# MC10_Tape.net
KiCad netlist of a schematic drawn in EAGLE
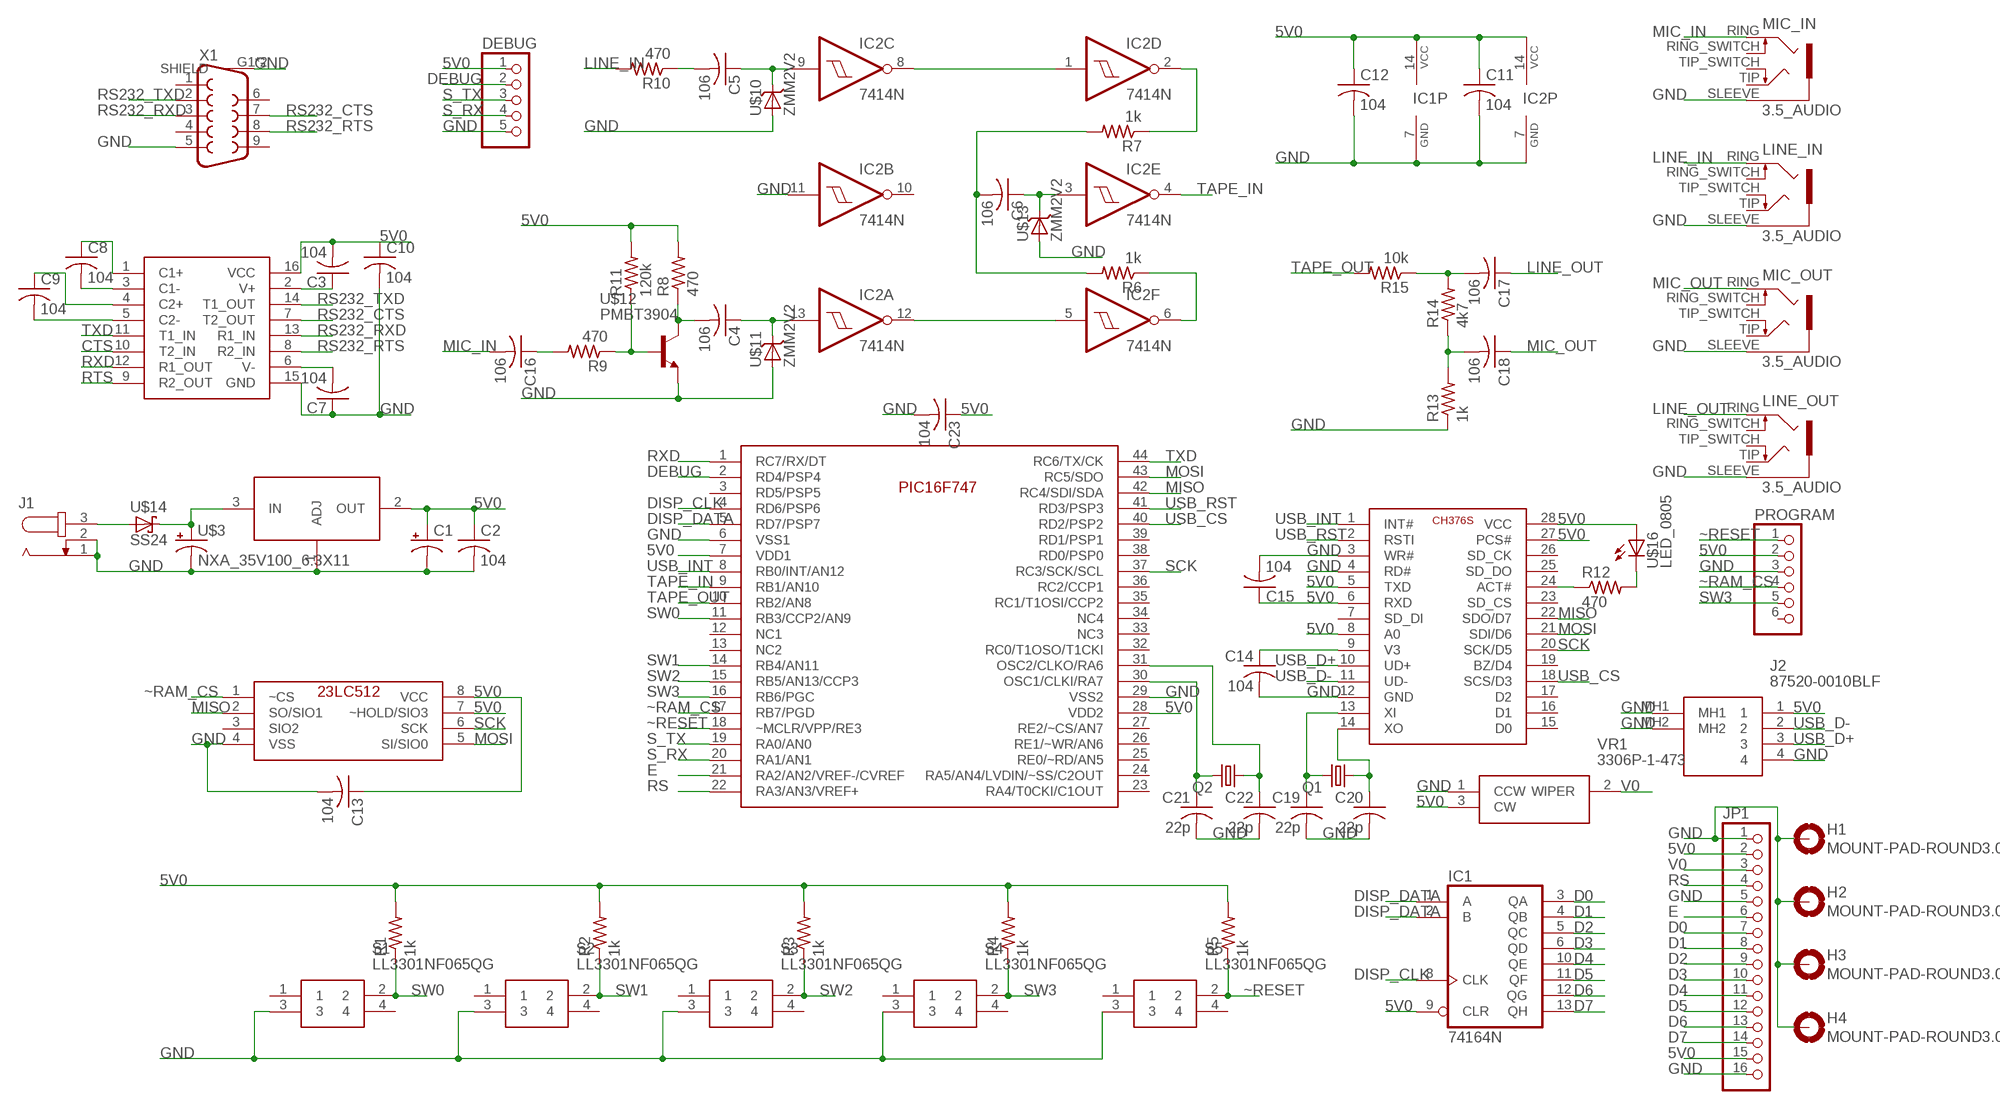
[diagram p0: schematic, sheet 1]

(export (version "E")
  (design (tool "Eeschema 10.0.6"))
  (components
    (comp (ref "C1")
      (value "CPOL-USUD-6,3X5,8")
      (footprint "eagle-import:UD-6,3X5,8_NICHICON")
      (libsource (lib "eagle-import") (part "CPOL-USUD-6,3X5,8"))
    )
    (comp (ref "C2")
      (value "104")
      (footprint "eagle-import:C0805")
      (libsource (lib "eagle-import") (part "C-USC0805"))
    )
    (comp (ref "C3")
      (value "104")
      (footprint "eagle-import:C0805")
      (libsource (lib "eagle-import") (part "C-USC0805"))
    )
    (comp (ref "C4")
      (value "106")
      (footprint "eagle-import:C1206")
      (libsource (lib "eagle-import") (part "C-USC1206"))
    )
    (comp (ref "C5")
      (value "106")
      (footprint "eagle-import:C1206")
      (libsource (lib "eagle-import") (part "C-USC1206"))
    )
    (comp (ref "C6")
      (value "106")
      (footprint "eagle-import:C1206")
      (libsource (lib "eagle-import") (part "C-USC1206"))
    )
    (comp (ref "C7")
      (value "104")
      (footprint "eagle-import:C0805")
      (libsource (lib "eagle-import") (part "C-USC0805"))
    )
    (comp (ref "C8")
      (value "104")
      (footprint "eagle-import:C0805")
      (libsource (lib "eagle-import") (part "C-USC0805"))
    )
    (comp (ref "C9")
      (value "104")
      (footprint "eagle-import:C0805")
      (libsource (lib "eagle-import") (part "C-USC0805"))
    )
    (comp (ref "C10")
      (value "104")
      (footprint "eagle-import:C0805")
      (libsource (lib "eagle-import") (part "C-USC0805"))
    )
    (comp (ref "C11")
      (value "104")
      (footprint "eagle-import:C0805")
      (libsource (lib "eagle-import") (part "C-USC0805"))
    )
    (comp (ref "C12")
      (value "104")
      (footprint "eagle-import:C0805")
      (libsource (lib "eagle-import") (part "C-USC0805"))
    )
    (comp (ref "C13")
      (value "104")
      (footprint "eagle-import:C0805")
      (libsource (lib "eagle-import") (part "C-USC0805"))
    )
    (comp (ref "C14")
      (value "104")
      (footprint "eagle-import:C0805")
      (libsource (lib "eagle-import") (part "C-USC0805"))
    )
    (comp (ref "C15")
      (value "104")
      (footprint "eagle-import:C0805")
      (libsource (lib "eagle-import") (part "C-USC0805"))
    )
    (comp (ref "C16")
      (value "106")
      (footprint "eagle-import:C1206")
      (libsource (lib "eagle-import") (part "C-USC1206"))
    )
    (comp (ref "C17")
      (value "106")
      (footprint "eagle-import:C1206")
      (libsource (lib "eagle-import") (part "C-USC1206"))
    )
    (comp (ref "C18")
      (value "106")
      (footprint "eagle-import:C1206")
      (libsource (lib "eagle-import") (part "C-USC1206"))
    )
    (comp (ref "C19")
      (value "22p")
      (footprint "eagle-import:C0805")
      (libsource (lib "eagle-import") (part "C-USC0805"))
    )
    (comp (ref "C20")
      (value "22p")
      (footprint "eagle-import:C0805")
      (libsource (lib "eagle-import") (part "C-USC0805"))
    )
    (comp (ref "C21")
      (value "22p")
      (footprint "eagle-import:C0805")
      (libsource (lib "eagle-import") (part "C-USC0805"))
    )
    (comp (ref "C22")
      (value "22p")
      (footprint "eagle-import:C0805")
      (libsource (lib "eagle-import") (part "C-USC0805"))
    )
    (comp (ref "C23")
      (value "104")
      (footprint "eagle-import:C0805")
      (libsource (lib "eagle-import") (part "C-USC0805"))
    )
    (comp (ref "DEBUG")
      (value "PINHD-1X5")
      (footprint "eagle-import:1X05")
      (libsource (lib "eagle-import") (part "PINHD-1X5"))
    )
    (comp (ref "H1")
      (value "MOUNT-PAD-ROUND3.0")
      (footprint "eagle-import:3,0-PAD")
      (libsource (lib "eagle-import") (part "MOUNT-PAD-ROUND3.0"))
    )
    (comp (ref "H2")
      (value "MOUNT-PAD-ROUND3.0")
      (footprint "eagle-import:3,0-PAD")
      (libsource (lib "eagle-import") (part "MOUNT-PAD-ROUND3.0"))
    )
    (comp (ref "H3")
      (value "MOUNT-PAD-ROUND3.0")
      (footprint "eagle-import:3,0-PAD")
      (libsource (lib "eagle-import") (part "MOUNT-PAD-ROUND3.0"))
    )
    (comp (ref "H4")
      (value "MOUNT-PAD-ROUND3.0")
      (footprint "eagle-import:3,0-PAD")
      (libsource (lib "eagle-import") (part "MOUNT-PAD-ROUND3.0"))
    )
    (comp (ref "IC1")
      (value "74164N")
      (footprint "eagle-import:DIL14")
      (libsource (lib "eagle-import") (part "74164N"))
    )
    (comp (ref "IC2")
      (value "7414N")
      (footprint "eagle-import:DIL14")
      (libsource (lib "eagle-import") (part "7414N"))
    )
    (comp (ref "J1")
      (value "JACK-PLUG0")
      (footprint "eagle-import:SPC4077")
      (libsource (lib "eagle-import") (part "JACK-PLUG0"))
    )
    (comp (ref "J2")
      (value "87520-0010BLF")
      (footprint "eagle-import:875200010BLF")
      (fields (field (name "MOUSER_PART_NUMBER") "649-87520-0010BLF"))
      (libsource (lib "eagle-import") (part "87520-0010BLF"))
    )
    (comp (ref "JP1")
      (value "PINHD-1X16")
      (footprint "eagle-import:1X16")
      (libsource (lib "eagle-import") (part "PINHD-1X16"))
    )
    (comp (ref "LINE_IN")
      (value "3.5_AUDIO")
      (footprint "eagle-import:3.5_AUDIO")
      (libsource (lib "eagle-import") (part "3.5_AUDIO"))
    )
    (comp (ref "LINE_OUT")
      (value "3.5_AUDIO")
      (footprint "eagle-import:3.5_AUDIO")
      (libsource (lib "eagle-import") (part "3.5_AUDIO"))
    )
    (comp (ref "MIC_IN")
      (value "3.5_AUDIO")
      (footprint "eagle-import:3.5_AUDIO")
      (libsource (lib "eagle-import") (part "3.5_AUDIO"))
    )
    (comp (ref "MIC_OUT")
      (value "3.5_AUDIO")
      (footprint "eagle-import:3.5_AUDIO")
      (libsource (lib "eagle-import") (part "3.5_AUDIO"))
    )
    (comp (ref "PROGRAM")
      (value "PINHD-1X6")
      (footprint "eagle-import:1X06")
      (libsource (lib "eagle-import") (part "PINHD-1X6"))
    )
    (comp (ref "Q1")
      (value "CRYSTALHC49S")
      (footprint "eagle-import:HC49_S")
      (libsource (lib "eagle-import") (part "CRYSTALHC49S"))
    )
    (comp (ref "Q2")
      (value "CRYSTALHC49S")
      (footprint "eagle-import:HC49_S")
      (libsource (lib "eagle-import") (part "CRYSTALHC49S"))
    )
    (comp (ref "R1")
      (value "1k")
      (footprint "eagle-import:M0805")
      (libsource (lib "eagle-import") (part "R-US_M0805"))
    )
    (comp (ref "R2")
      (value "1k")
      (footprint "eagle-import:M0805")
      (libsource (lib "eagle-import") (part "R-US_M0805"))
    )
    (comp (ref "R3")
      (value "1k")
      (footprint "eagle-import:M0805")
      (libsource (lib "eagle-import") (part "R-US_M0805"))
    )
    (comp (ref "R4")
      (value "1k")
      (footprint "eagle-import:M0805")
      (libsource (lib "eagle-import") (part "R-US_M0805"))
    )
    (comp (ref "R5")
      (value "1k")
      (footprint "eagle-import:M0805")
      (libsource (lib "eagle-import") (part "R-US_M0805"))
    )
    (comp (ref "R6")
      (value "1k")
      (footprint "eagle-import:M0805")
      (libsource (lib "eagle-import") (part "R-US_M0805"))
    )
    (comp (ref "R7")
      (value "1k")
      (footprint "eagle-import:M0805")
      (libsource (lib "eagle-import") (part "R-US_M0805"))
    )
    (comp (ref "R8")
      (value "470")
      (footprint "eagle-import:M0805")
      (libsource (lib "eagle-import") (part "R-US_M0805"))
    )
    (comp (ref "R9")
      (value "470")
      (footprint "eagle-import:M0805")
      (libsource (lib "eagle-import") (part "R-US_M0805"))
    )
    (comp (ref "R10")
      (value "470")
      (footprint "eagle-import:M0805")
      (libsource (lib "eagle-import") (part "R-US_M0805"))
    )
    (comp (ref "R11")
      (value "120k")
      (footprint "eagle-import:M0805")
      (libsource (lib "eagle-import") (part "R-US_M0805"))
    )
    (comp (ref "R12")
      (value "470")
      (footprint "eagle-import:M0805")
      (libsource (lib "eagle-import") (part "R-US_M0805"))
    )
    (comp (ref "R13")
      (value "1k")
      (footprint "eagle-import:M0805")
      (libsource (lib "eagle-import") (part "R-US_M0805"))
    )
    (comp (ref "R14")
      (value "4k7")
      (footprint "eagle-import:M0805")
      (libsource (lib "eagle-import") (part "R-US_M0805"))
    )
    (comp (ref "R15")
      (value "10k")
      (footprint "eagle-import:M0805")
      (libsource (lib "eagle-import") (part "R-US_M0805"))
    )
    (comp (ref "S1")
      (value "LL3301NF065QG")
      (footprint "eagle-import:LL3301NF065QG")
      (fields (field (name "MOUSER_PART_NUMBER") "612-LL3301NF065QG"))
      (libsource (lib "eagle-import") (part "LL3301NF065QG"))
    )
    (comp (ref "S2")
      (value "LL3301NF065QG")
      (footprint "eagle-import:LL3301NF065QG")
      (fields (field (name "MOUSER_PART_NUMBER") "612-LL3301NF065QG"))
      (libsource (lib "eagle-import") (part "LL3301NF065QG"))
    )
    (comp (ref "S3")
      (value "LL3301NF065QG")
      (footprint "eagle-import:LL3301NF065QG")
      (fields (field (name "MOUSER_PART_NUMBER") "612-LL3301NF065QG"))
      (libsource (lib "eagle-import") (part "LL3301NF065QG"))
    )
    (comp (ref "S4")
      (value "LL3301NF065QG")
      (footprint "eagle-import:LL3301NF065QG")
      (fields (field (name "MOUSER_PART_NUMBER") "612-LL3301NF065QG"))
      (libsource (lib "eagle-import") (part "LL3301NF065QG"))
    )
    (comp (ref "S5")
      (value "LL3301NF065QG")
      (footprint "eagle-import:LL3301NF065QG")
      (fields (field (name "MOUSER_PART_NUMBER") "612-LL3301NF065QG"))
      (libsource (lib "eagle-import") (part "LL3301NF065QG"))
    )
    (comp (ref "U$1")
      (value "PIC16F747-IPT")
      (footprint "eagle-import:TQFP44")
      (libsource (lib "eagle-import") (part "PIC16F747-IPT"))
    )
    (comp (ref "U$2")
      (value "LM1086")
      (footprint "eagle-import:D2PACK")
      (libsource (lib "eagle-import") (part "LM1086"))
    )
    (comp (ref "U$3")
      (value "NXA_35V100_6.3X11")
      (footprint "eagle-import:NXA_35V100_6.3X11")
      (libsource (lib "eagle-import") (part "NXA_35V100_6.3X11"))
    )
    (comp (ref "U$4")
      (value "23LC512T-ISN")
      (footprint "eagle-import:SO08")
      (libsource (lib "eagle-import") (part "23LC512T-ISN"))
    )
    (comp (ref "U$9")
      (value "SP232")
      (footprint "eagle-import:SOP16")
      (libsource (lib "eagle-import") (part "SP232"))
    )
    (comp (ref "U$10")
      (value "ZMM2V2")
      (footprint "eagle-import:SOD80C")
      (libsource (lib "eagle-import") (part "ZMM2V2"))
    )
    (comp (ref "U$11")
      (value "ZMM2V2")
      (footprint "eagle-import:SOD80C")
      (libsource (lib "eagle-import") (part "ZMM2V2"))
    )
    (comp (ref "U$12")
      (value "PMBT3904")
      (footprint "eagle-import:SOT23")
      (libsource (lib "eagle-import") (part "PMBT3904"))
    )
    (comp (ref "U$13")
      (value "ZMM2V2")
      (footprint "eagle-import:SOD80C")
      (libsource (lib "eagle-import") (part "ZMM2V2"))
    )
    (comp (ref "U$14")
      (value "SS24")
      (footprint "eagle-import:SMA-DO214AC")
      (libsource (lib "eagle-import") (part "SS24"))
    )
    (comp (ref "U$15")
      (value "CH376S")
      (footprint "eagle-import:SOP28")
      (libsource (lib "eagle-import") (part "CH376S"))
    )
    (comp (ref "U$16")
      (value "LED_0805")
      (footprint "eagle-import:CHIP-LED0805")
      (libsource (lib "eagle-import") (part "LED_0805"))
    )
    (comp (ref "VR1")
      (value "3306P-1-473")
      (footprint "eagle-import:3306P1104")
      (fields (field (name "MOUSER_PART_NUMBER") "652-3306P-1-473"))
      (libsource (lib "eagle-import") (part "3306P-1-473"))
    )
    (comp (ref "X1")
      (value "F09HP")
      (footprint "eagle-import:F09HP")
      (libsource (lib "eagle-import") (part "F09HP"))
    )
  )
  (nets
    (net (code "1") (name "/5V0") (class "Default")
      (node (ref "C1") (pin "+") (pinfunction "+_+") (pintype "passive"))
      (node (ref "C10") (pin "1") (pinfunction "1_1") (pintype "passive"))
      (node (ref "C11") (pin "1") (pinfunction "1_1") (pintype "passive"))
      (node (ref "C12") (pin "1") (pinfunction "1_1") (pintype "passive"))
      (node (ref "C13") (pin "1") (pinfunction "1_1") (pintype "passive"))
      (node (ref "C15") (pin "1") (pinfunction "1_1") (pintype "passive"))
      (node (ref "C2") (pin "1") (pinfunction "1_1") (pintype "passive"))
      (node (ref "C23") (pin "1") (pinfunction "1_1") (pintype "passive"))
      (node (ref "C3") (pin "2") (pinfunction "2_2") (pintype "passive"))
      (node (ref "DEBUG") (pin "1") (pinfunction "1_1") (pintype "passive"))
      (node (ref "IC1") (pin "14") (pinfunction "VCC_14") (pintype "power_in"))
      (node (ref "IC1") (pin "9") (pinfunction "CLR_9") (pintype "input"))
      (node (ref "IC2") (pin "14") (pinfunction "VCC_14") (pintype "power_in"))
      (node (ref "J2") (pin "1") (pinfunction "1_1") (pintype "bidirectional"))
      (node (ref "JP1") (pin "15") (pinfunction "15_15") (pintype "passive"))
      (node (ref "JP1") (pin "2") (pinfunction "2_2") (pintype "passive"))
      (node (ref "PROGRAM") (pin "2") (pinfunction "2_2") (pintype "passive"))
      (node (ref "R1") (pin "2") (pinfunction "2_2") (pintype "passive"))
      (node (ref "R11") (pin "2") (pinfunction "2_2") (pintype "passive"))
      (node (ref "R2") (pin "2") (pinfunction "2_2") (pintype "passive"))
      (node (ref "R3") (pin "2") (pinfunction "2_2") (pintype "passive"))
      (node (ref "R4") (pin "2") (pinfunction "2_2") (pintype "passive"))
      (node (ref "R5") (pin "2") (pinfunction "2_2") (pintype "passive"))
      (node (ref "R8") (pin "2") (pinfunction "2_2") (pintype "passive"))
      (node (ref "U$1") (pin "28") (pinfunction "VDD2_28") (pintype "bidirectional"))
      (node (ref "U$1") (pin "7") (pinfunction "VDD1_7") (pintype "bidirectional"))
      (node (ref "U$15") (pin "27") (pinfunction "PCS#_27") (pintype "bidirectional"))
      (node (ref "U$15") (pin "28") (pinfunction "VCC_28") (pintype "bidirectional"))
      (node (ref "U$15") (pin "5") (pinfunction "TXD_5") (pintype "bidirectional"))
      (node (ref "U$15") (pin "6") (pinfunction "RXD_6") (pintype "bidirectional"))
      (node (ref "U$15") (pin "8") (pinfunction "A0_8") (pintype "bidirectional"))
      (node (ref "U$16") (pin "A") (pinfunction "A_A") (pintype "passive"))
      (node (ref "U$2") (pin "2") (pinfunction "OUT_2") (pintype "bidirectional"))
      (node (ref "U$4") (pin "7") (pinfunction "~{HOLD/SIO3}_7") (pintype "bidirectional"))
      (node (ref "U$4") (pin "8") (pinfunction "VCC_8") (pintype "bidirectional"))
      (node (ref "U$9") (pin "16") (pinfunction "VCC_16") (pintype "bidirectional"))
      (node (ref "VR1") (pin "3") (pinfunction "CW_3") (pintype "bidirectional"))
    )
    (net (code "2") (name "/CTS") (class "Default")
      (node (ref "U$9") (pin "10") (pinfunction "T2_IN_10") (pintype "bidirectional"))
    )
    (net (code "3") (name "/D0") (class "Default")
      (node (ref "IC1") (pin "3") (pinfunction "QA_3") (pintype "output"))
      (node (ref "JP1") (pin "7") (pinfunction "7_7") (pintype "passive"))
    )
    (net (code "4") (name "/D1") (class "Default")
      (node (ref "IC1") (pin "4") (pinfunction "QB_4") (pintype "output"))
      (node (ref "JP1") (pin "8") (pinfunction "8_8") (pintype "passive"))
    )
    (net (code "5") (name "/D2") (class "Default")
      (node (ref "IC1") (pin "5") (pinfunction "QC_5") (pintype "output"))
      (node (ref "JP1") (pin "9") (pinfunction "9_9") (pintype "passive"))
    )
    (net (code "6") (name "/D3") (class "Default")
      (node (ref "IC1") (pin "6") (pinfunction "QD_6") (pintype "output"))
      (node (ref "JP1") (pin "10") (pinfunction "10_10") (pintype "passive"))
    )
    (net (code "7") (name "/D4") (class "Default")
      (node (ref "IC1") (pin "10") (pinfunction "QE_10") (pintype "output"))
      (node (ref "JP1") (pin "11") (pinfunction "11_11") (pintype "passive"))
    )
    (net (code "8") (name "/D5") (class "Default")
      (node (ref "IC1") (pin "11") (pinfunction "QF_11") (pintype "output"))
      (node (ref "JP1") (pin "12") (pinfunction "12_12") (pintype "passive"))
    )
    (net (code "9") (name "/D6") (class "Default")
      (node (ref "IC1") (pin "12") (pinfunction "QG_12") (pintype "output"))
      (node (ref "JP1") (pin "13") (pinfunction "13_13") (pintype "passive"))
    )
    (net (code "10") (name "/D7") (class "Default")
      (node (ref "IC1") (pin "13") (pinfunction "QH_13") (pintype "output"))
      (node (ref "JP1") (pin "14") (pinfunction "14_14") (pintype "passive"))
    )
    (net (code "11") (name "/DEBUG") (class "Default")
      (node (ref "DEBUG") (pin "2") (pinfunction "2_2") (pintype "passive"))
      (node (ref "U$1") (pin "2") (pinfunction "RD4/PSP4_2") (pintype "bidirectional"))
    )
    (net (code "12") (name "/DISP_CLK") (class "Default")
      (node (ref "IC1") (pin "8") (pinfunction "CLK_8") (pintype "input"))
      (node (ref "U$1") (pin "4") (pinfunction "RD6/PSP6_4") (pintype "bidirectional"))
    )
    (net (code "13") (name "/DISP_DATA") (class "Default")
      (node (ref "IC1") (pin "1") (pinfunction "A_1") (pintype "input"))
      (node (ref "IC1") (pin "2") (pinfunction "B_2") (pintype "input"))
      (node (ref "U$1") (pin "5") (pinfunction "RD7/PSP7_5") (pintype "bidirectional"))
    )
    (net (code "14") (name "/E") (class "Default")
      (node (ref "JP1") (pin "6") (pinfunction "6_6") (pintype "passive"))
      (node (ref "U$1") (pin "21") (pinfunction "RA2/AN2/VREF-/CVREF_21") (pintype "bidirectional"))
    )
    (net (code "15") (name "/GND") (class "Default")
      (node (ref "C1") (pin "-") (pinfunction "-_-") (pintype "passive"))
      (node (ref "C10") (pin "2") (pinfunction "2_2") (pintype "passive"))
      (node (ref "C11") (pin "2") (pinfunction "2_2") (pintype "passive"))
      (node (ref "C12") (pin "2") (pinfunction "2_2") (pintype "passive"))
      (node (ref "C13") (pin "2") (pinfunction "2_2") (pintype "passive"))
      (node (ref "C14") (pin "2") (pinfunction "2_2") (pintype "passive"))
      (node (ref "C15") (pin "2") (pinfunction "2_2") (pintype "passive"))
      (node (ref "C19") (pin "2") (pinfunction "2_2") (pintype "passive"))
      (node (ref "C2") (pin "2") (pinfunction "2_2") (pintype "passive"))
      (node (ref "C20") (pin "2") (pinfunction "2_2") (pintype "passive"))
      (node (ref "C21") (pin "2") (pinfunction "2_2") (pintype "passive"))
      (node (ref "C22") (pin "2") (pinfunction "2_2") (pintype "passive"))
      (node (ref "C23") (pin "2") (pinfunction "2_2") (pintype "passive"))
      (node (ref "C7") (pin "1") (pinfunction "1_1") (pintype "passive"))
      (node (ref "DEBUG") (pin "5") (pinfunction "5_5") (pintype "passive"))
      (node (ref "H1") (pin "B3,0") (pinfunction "MOUNT_B3,0") (pintype "passive"))
      (node (ref "H2") (pin "B3,0") (pinfunction "MOUNT_B3,0") (pintype "passive"))
      (node (ref "H3") (pin "B3,0") (pinfunction "MOUNT_B3,0") (pintype "passive"))
      (node (ref "H4") (pin "B3,0") (pinfunction "MOUNT_B3,0") (pintype "passive"))
      (node (ref "IC1") (pin "7") (pinfunction "GND_7") (pintype "power_in"))
      (node (ref "IC2") (pin "11") (pinfunction "I_11") (pintype "input"))
      (node (ref "IC2") (pin "7") (pinfunction "GND_7") (pintype "power_in"))
      (node (ref "J1") (pin "1") (pinfunction "1_1") (pintype "passive"))
      (node (ref "J1") (pin "2") (pinfunction "2_2") (pintype "passive"))
      (node (ref "J2") (pin "4") (pinfunction "4_4") (pintype "bidirectional"))
      (node (ref "J2") (pin "MH1") (pinfunction "MH1_MH1") (pintype "bidirectional"))
      (node (ref "J2") (pin "MH2") (pinfunction "MH2_MH2") (pintype "bidirectional"))
      (node (ref "JP1") (pin "1") (pinfunction "1_1") (pintype "passive"))
      (node (ref "JP1") (pin "16") (pinfunction "16_16") (pintype "passive"))
      (node (ref "JP1") (pin "5") (pinfunction "5_5") (pintype "passive"))
      (node (ref "LINE_IN") (pin "SLEEVE") (pinfunction "SLEEVE_SLEEVE") (pintype "passive"))
      (node (ref "LINE_OUT") (pin "SLEEVE") (pinfunction "SLEEVE_SLEEVE") (pintype "passive"))
      (node (ref "MIC_IN") (pin "SLEEVE") (pinfunction "SLEEVE_SLEEVE") (pintype "passive"))
      (node (ref "MIC_OUT") (pin "SLEEVE") (pinfunction "SLEEVE_SLEEVE") (pintype "passive"))
      (node (ref "PROGRAM") (pin "3") (pinfunction "3_3") (pintype "passive"))
      (node (ref "R13") (pin "1") (pinfunction "1_1") (pintype "passive"))
      (node (ref "S1") (pin "3") (pinfunction "3_3") (pintype "bidirectional"))
      (node (ref "S2") (pin "3") (pinfunction "3_3") (pintype "bidirectional"))
      (node (ref "S3") (pin "3") (pinfunction "3_3") (pintype "bidirectional"))
      (node (ref "S4") (pin "3") (pinfunction "3_3") (pintype "bidirectional"))
      (node (ref "S5") (pin "3") (pinfunction "3_3") (pintype "bidirectional"))
      (node (ref "U$1") (pin "29") (pinfunction "VSS2_29") (pintype "bidirectional"))
      (node (ref "U$1") (pin "6") (pinfunction "VSS1_6") (pintype "bidirectional"))
      (node (ref "U$10") (pin "A") (pinfunction "A_A") (pintype "passive"))
      (node (ref "U$11") (pin "A") (pinfunction "A_A") (pintype "passive"))
      (node (ref "U$12") (pin "2") (pinfunction "E_2") (pintype "passive"))
      (node (ref "U$13") (pin "A") (pinfunction "A_A") (pintype "passive"))
      (node (ref "U$15") (pin "12") (pinfunction "GND_12") (pintype "bidirectional"))
      (node (ref "U$15") (pin "3") (pinfunction "WR#_3") (pintype "bidirectional"))
      (node (ref "U$15") (pin "4") (pinfunction "RD#_4") (pintype "bidirectional"))
      (node (ref "U$2") (pin "1") (pinfunction "ADJ_1") (pintype "bidirectional"))
      (node (ref "U$3") (pin "P$1") (pinfunction "-_P$1") (pintype "passive"))
      (node (ref "U$4") (pin "4") (pinfunction "VSS_4") (pintype "bidirectional"))
      (node (ref "U$9") (pin "15") (pinfunction "GND_15") (pintype "bidirectional"))
      (node (ref "VR1") (pin "1") (pinfunction "CCW_1") (pintype "bidirectional"))
      (node (ref "X1") (pin "5") (pinfunction "5_5") (pintype "passive"))
      (node (ref "X1") (pin "G1") (pinfunction "SHIELD_G1") (pintype "bidirectional"))
      (node (ref "X1") (pin "G2") (pinfunction "SHIELD_G2") (pintype "bidirectional"))
    )
    (net (code "16") (name "/LINE_IN") (class "Default")
      (node (ref "LINE_IN") (pin "RING") (pinfunction "RING_RING") (pintype "passive"))
      (node (ref "R10") (pin "2") (pinfunction "2_2") (pintype "passive"))
    )
    (net (code "17") (name "/LINE_OUT") (class "Default")
      (node (ref "C17") (pin "1") (pinfunction "1_1") (pintype "passive"))
      (node (ref "LINE_OUT") (pin "RING") (pinfunction "RING_RING") (pintype "passive"))
    )
    (net (code "18") (name "/MIC_IN") (class "Default")
      (node (ref "C16") (pin "2") (pinfunction "2_2") (pintype "passive"))
      (node (ref "MIC_IN") (pin "RING") (pinfunction "RING_RING") (pintype "passive"))
    )
    (net (code "19") (name "/MIC_OUT") (class "Default")
      (node (ref "C18") (pin "1") (pinfunction "1_1") (pintype "passive"))
      (node (ref "MIC_OUT") (pin "RING") (pinfunction "RING_RING") (pintype "passive"))
    )
    (net (code "20") (name "/MISO") (class "Default")
      (node (ref "U$1") (pin "42") (pinfunction "RC4/SDI/SDA_42") (pintype "bidirectional"))
      (node (ref "U$15") (pin "22") (pinfunction "SDO/D7_22") (pintype "bidirectional"))
      (node (ref "U$4") (pin "2") (pinfunction "SO/SIO1_2") (pintype "bidirectional"))
    )
    (net (code "21") (name "/MOSI") (class "Default")
      (node (ref "U$1") (pin "43") (pinfunction "RC5/SDO_43") (pintype "bidirectional"))
      (node (ref "U$15") (pin "21") (pinfunction "SDI/D6_21") (pintype "bidirectional"))
      (node (ref "U$4") (pin "5") (pinfunction "SI/SIO0_5") (pintype "bidirectional"))
    )
    (net (code "22") (name "/RS") (class "Default")
      (node (ref "JP1") (pin "4") (pinfunction "4_4") (pintype "passive"))
      (node (ref "U$1") (pin "22") (pinfunction "RA3/AN3/VREF+_22") (pintype "bidirectional"))
    )
    (net (code "23") (name "/RS232_CTS") (class "Default")
      (node (ref "U$9") (pin "7") (pinfunction "T2_OUT_7") (pintype "bidirectional"))
      (node (ref "X1") (pin "7") (pinfunction "7_7") (pintype "passive"))
    )
    (net (code "24") (name "/RS232_RTS") (class "Default")
      (node (ref "U$9") (pin "8") (pinfunction "R2_IN_8") (pintype "bidirectional"))
      (node (ref "X1") (pin "8") (pinfunction "8_8") (pintype "passive"))
    )
    (net (code "25") (name "/RS232_RXD") (class "Default")
      (node (ref "U$9") (pin "13") (pinfunction "R1_IN_13") (pintype "bidirectional"))
      (node (ref "X1") (pin "3") (pinfunction "3_3") (pintype "passive"))
    )
    (net (code "26") (name "/RS232_TXD") (class "Default")
      (node (ref "U$9") (pin "14") (pinfunction "T1_OUT_14") (pintype "bidirectional"))
      (node (ref "X1") (pin "2") (pinfunction "2_2") (pintype "passive"))
    )
    (net (code "27") (name "/RTS") (class "Default")
      (node (ref "U$9") (pin "9") (pinfunction "R2_OUT_9") (pintype "bidirectional"))
    )
    (net (code "28") (name "/RXD") (class "Default")
      (node (ref "U$1") (pin "1") (pinfunction "RC7/RX/DT_1") (pintype "bidirectional"))
      (node (ref "U$9") (pin "12") (pinfunction "R1_OUT_12") (pintype "bidirectional"))
    )
    (net (code "29") (name "/SCK") (class "Default")
      (node (ref "U$1") (pin "37") (pinfunction "RC3/SCK/SCL_37") (pintype "bidirectional"))
      (node (ref "U$15") (pin "20") (pinfunction "SCK/D5_20") (pintype "bidirectional"))
      (node (ref "U$4") (pin "6") (pinfunction "SCK_6") (pintype "bidirectional"))
    )
    (net (code "30") (name "/SW0") (class "Default")
      (node (ref "R1") (pin "1") (pinfunction "1_1") (pintype "passive"))
      (node (ref "S1") (pin "2") (pinfunction "2_2") (pintype "bidirectional"))
      (node (ref "U$1") (pin "11") (pinfunction "RB3/CCP2/AN9_11") (pintype "bidirectional"))
    )
    (net (code "31") (name "/SW1") (class "Default")
      (node (ref "R2") (pin "1") (pinfunction "1_1") (pintype "passive"))
      (node (ref "S2") (pin "2") (pinfunction "2_2") (pintype "bidirectional"))
      (node (ref "U$1") (pin "14") (pinfunction "RB4/AN11_14") (pintype "bidirectional"))
    )
    (net (code "32") (name "/SW2") (class "Default")
      (node (ref "R3") (pin "1") (pinfunction "1_1") (pintype "passive"))
      (node (ref "S3") (pin "2") (pinfunction "2_2") (pintype "bidirectional"))
      (node (ref "U$1") (pin "15") (pinfunction "RB5/AN13/CCP3_15") (pintype "bidirectional"))
    )
    (net (code "33") (name "/SW3") (class "Default")
      (node (ref "PROGRAM") (pin "5") (pinfunction "5_5") (pintype "passive"))
      (node (ref "R4") (pin "1") (pinfunction "1_1") (pintype "passive"))
      (node (ref "S4") (pin "2") (pinfunction "2_2") (pintype "bidirectional"))
      (node (ref "U$1") (pin "16") (pinfunction "RB6/PGC_16") (pintype "bidirectional"))
    )
    (net (code "34") (name "/S_RX") (class "Default")
      (node (ref "DEBUG") (pin "4") (pinfunction "4_4") (pintype "passive"))
      (node (ref "U$1") (pin "20") (pinfunction "RA1/AN1_20") (pintype "bidirectional"))
    )
    (net (code "35") (name "/S_TX") (class "Default")
      (node (ref "DEBUG") (pin "3") (pinfunction "3_3") (pintype "passive"))
      (node (ref "U$1") (pin "19") (pinfunction "RA0/AN0_19") (pintype "bidirectional"))
    )
    (net (code "36") (name "/TAPE_IN") (class "Default")
      (node (ref "IC2") (pin "4") (pinfunction "O_4") (pintype "output"))
      (node (ref "U$1") (pin "9") (pinfunction "RB1/AN10_9") (pintype "bidirectional"))
    )
    (net (code "37") (name "/TAPE_OUT") (class "Default")
      (node (ref "R15") (pin "2") (pinfunction "2_2") (pintype "passive"))
      (node (ref "U$1") (pin "10") (pinfunction "RB2/AN8_10") (pintype "bidirectional"))
    )
    (net (code "38") (name "/TXD") (class "Default")
      (node (ref "U$1") (pin "44") (pinfunction "RC6/TX/CK_44") (pintype "bidirectional"))
      (node (ref "U$9") (pin "11") (pinfunction "T1_IN_11") (pintype "bidirectional"))
    )
    (net (code "39") (name "/USB_CS") (class "Default")
      (node (ref "U$1") (pin "40") (pinfunction "RD2/PSP2_40") (pintype "bidirectional"))
      (node (ref "U$15") (pin "18") (pinfunction "SCS/D3_18") (pintype "bidirectional"))
    )
    (net (code "40") (name "/USB_D+") (class "Default")
      (node (ref "J2") (pin "3") (pinfunction "3_3") (pintype "bidirectional"))
      (node (ref "U$15") (pin "10") (pinfunction "UD+_10") (pintype "bidirectional"))
    )
    (net (code "41") (name "/USB_D-") (class "Default")
      (node (ref "J2") (pin "2") (pinfunction "2_2") (pintype "bidirectional"))
      (node (ref "U$15") (pin "11") (pinfunction "UD-_11") (pintype "bidirectional"))
    )
    (net (code "42") (name "/USB_INT") (class "Default")
      (node (ref "U$1") (pin "8") (pinfunction "RB0/INT/AN12_8") (pintype "bidirectional"))
      (node (ref "U$15") (pin "1") (pinfunction "INT#_1") (pintype "bidirectional"))
    )
    (net (code "43") (name "/USB_RST") (class "Default")
      (node (ref "U$1") (pin "41") (pinfunction "RD3/PSP3_41") (pintype "bidirectional"))
      (node (ref "U$15") (pin "2") (pinfunction "RSTI_2") (pintype "bidirectional"))
    )
    (net (code "44") (name "/V0") (class "Default")
      (node (ref "JP1") (pin "3") (pinfunction "3_3") (pintype "passive"))
      (node (ref "VR1") (pin "2") (pinfunction "WIPER_2") (pintype "bidirectional"))
    )
    (net (code "45") (name "/~{RAM_CS}") (class "Default")
      (node (ref "PROGRAM") (pin "4") (pinfunction "4_4") (pintype "passive"))
      (node (ref "U$1") (pin "17") (pinfunction "RB7/PGD_17") (pintype "bidirectional"))
      (node (ref "U$4") (pin "1") (pinfunction "~{CS}_1") (pintype "bidirectional"))
    )
    (net (code "46") (name "/~{RESET}") (class "Default")
      (node (ref "PROGRAM") (pin "1") (pinfunction "1_1") (pintype "passive"))
      (node (ref "R5") (pin "1") (pinfunction "1_1") (pintype "passive"))
      (node (ref "S5") (pin "2") (pinfunction "2_2") (pintype "bidirectional"))
      (node (ref "U$1") (pin "18") (pinfunction "~{MCLR/VPP/RE3}_18") (pintype "bidirectional"))
    )
    (net (code "47") (name "Net-(C5-Pad2)") (class "Default")
      (node (ref "C5") (pin "2") (pinfunction "2_2") (pintype "passive"))
      (node (ref "R10") (pin "1") (pinfunction "1_1") (pintype "passive"))
    )
    (net (code "48") (name "Net-(C6-Pad2)") (class "Default")
      (node (ref "C6") (pin "2") (pinfunction "2_2") (pintype "passive"))
      (node (ref "R6") (pin "2") (pinfunction "2_2") (pintype "passive"))
      (node (ref "R7") (pin "2") (pinfunction "2_2") (pintype "passive"))
    )
    (net (code "49") (name "Net-(C16-Pad1)") (class "Default")
      (node (ref "C16") (pin "1") (pinfunction "1_1") (pintype "passive"))
      (node (ref "R9") (pin "2") (pinfunction "2_2") (pintype "passive"))
    )
    (net (code "50") (name "Net-(C17-Pad2)") (class "Default")
      (node (ref "C17") (pin "2") (pinfunction "2_2") (pintype "passive"))
      (node (ref "R14") (pin "2") (pinfunction "2_2") (pintype "passive"))
      (node (ref "R15") (pin "1") (pinfunction "1_1") (pintype "passive"))
    )
    (net (code "51") (name "Net-(C18-Pad2)") (class "Default")
      (node (ref "C18") (pin "2") (pinfunction "2_2") (pintype "passive"))
      (node (ref "R13") (pin "2") (pinfunction "2_2") (pintype "passive"))
      (node (ref "R14") (pin "1") (pinfunction "1_1") (pintype "passive"))
    )
    (net (code "52") (name "Net-(IC2A-I)") (class "Default")
      (node (ref "C4") (pin "1") (pinfunction "1_1") (pintype "passive"))
      (node (ref "IC2") (pin "13") (pinfunction "I_13") (pintype "input"))
      (node (ref "U$11") (pin "C") (pinfunction "C_C") (pintype "passive"))
    )
    (net (code "53") (name "Net-(IC2A-O)") (class "Default")
      (node (ref "IC2") (pin "12") (pinfunction "O_12") (pintype "output"))
      (node (ref "IC2") (pin "5") (pinfunction "I_5") (pintype "input"))
    )
    (net (code "54") (name "Net-(IC2C-I)") (class "Default")
      (node (ref "C5") (pin "1") (pinfunction "1_1") (pintype "passive"))
      (node (ref "IC2") (pin "9") (pinfunction "I_9") (pintype "input"))
      (node (ref "U$10") (pin "C") (pinfunction "C_C") (pintype "passive"))
    )
    (net (code "55") (name "Net-(IC2C-O)") (class "Default")
      (node (ref "IC2") (pin "1") (pinfunction "I_1") (pintype "input"))
      (node (ref "IC2") (pin "8") (pinfunction "O_8") (pintype "output"))
    )
    (net (code "56") (name "Net-(IC2D-O)") (class "Default")
      (node (ref "IC2") (pin "2") (pinfunction "O_2") (pintype "output"))
      (node (ref "R7") (pin "1") (pinfunction "1_1") (pintype "passive"))
    )
    (net (code "57") (name "Net-(IC2E-I)") (class "Default")
      (node (ref "C6") (pin "1") (pinfunction "1_1") (pintype "passive"))
      (node (ref "IC2") (pin "3") (pinfunction "I_3") (pintype "input"))
      (node (ref "U$13") (pin "C") (pinfunction "C_C") (pintype "passive"))
    )
    (net (code "58") (name "Net-(IC2F-O)") (class "Default")
      (node (ref "IC2") (pin "6") (pinfunction "O_6") (pintype "output"))
      (node (ref "R6") (pin "1") (pinfunction "1_1") (pintype "passive"))
    )
    (net (code "59") (name "Net-(J1-Pad3)") (class "Default")
      (node (ref "J1") (pin "3") (pinfunction "3_3") (pintype "passive"))
      (node (ref "U$14") (pin "A") (pinfunction "A_A") (pintype "passive"))
    )
    (net (code "60") (name "Net-(R12-Pad2)") (class "Default")
      (node (ref "R12") (pin "2") (pinfunction "2_2") (pintype "passive"))
      (node (ref "U$16") (pin "C") (pinfunction "C_C") (pintype "passive"))
    )
    (net (code "61") (name "Net-(U$1-OSC1{slash}CLKI{slash}RA7)") (class "Default")
      (node (ref "C21") (pin "1") (pinfunction "1_1") (pintype "passive"))
      (node (ref "Q2") (pin "2") (pinfunction "2_2") (pintype "passive"))
      (node (ref "U$1") (pin "30") (pinfunction "OSC1/CLKI/RA7_30") (pintype "bidirectional"))
    )
    (net (code "62") (name "Net-(U$1-OSC2{slash}CLKO{slash}RA6)") (class "Default")
      (node (ref "C22") (pin "1") (pinfunction "1_1") (pintype "passive"))
      (node (ref "Q2") (pin "1") (pinfunction "1_1") (pintype "passive"))
      (node (ref "U$1") (pin "31") (pinfunction "OSC2/CLKO/RA6_31") (pintype "bidirectional"))
    )
    (net (code "63") (name "Net-(U$9-C1+)") (class "Default")
      (node (ref "C8") (pin "1") (pinfunction "1_1") (pintype "passive"))
      (node (ref "U$9") (pin "1") (pinfunction "C1+_1") (pintype "bidirectional"))
    )
    (net (code "64") (name "Net-(U$9-C1-)") (class "Default")
      (node (ref "C8") (pin "2") (pinfunction "2_2") (pintype "passive"))
      (node (ref "U$9") (pin "3") (pinfunction "C1-_3") (pintype "bidirectional"))
    )
    (net (code "65") (name "Net-(U$9-C2+)") (class "Default")
      (node (ref "C9") (pin "1") (pinfunction "1_1") (pintype "passive"))
      (node (ref "U$9") (pin "4") (pinfunction "C2+_4") (pintype "bidirectional"))
    )
    (net (code "66") (name "Net-(U$9-C2-)") (class "Default")
      (node (ref "C9") (pin "2") (pinfunction "2_2") (pintype "passive"))
      (node (ref "U$9") (pin "5") (pinfunction "C2-_5") (pintype "bidirectional"))
    )
    (net (code "67") (name "Net-(U$9-V+)") (class "Default")
      (node (ref "C3") (pin "1") (pinfunction "1_1") (pintype "passive"))
      (node (ref "U$9") (pin "2") (pinfunction "V+_2") (pintype "bidirectional"))
    )
    (net (code "68") (name "Net-(U$9-V-)") (class "Default")
      (node (ref "C7") (pin "2") (pinfunction "2_2") (pintype "passive"))
      (node (ref "U$9") (pin "6") (pinfunction "V-_6") (pintype "bidirectional"))
    )
    (net (code "69") (name "Net-(U$12-B)") (class "Default")
      (node (ref "R11") (pin "1") (pinfunction "1_1") (pintype "passive"))
      (node (ref "R9") (pin "1") (pinfunction "1_1") (pintype "passive"))
      (node (ref "U$12") (pin "1") (pinfunction "B_1") (pintype "passive"))
    )
    (net (code "70") (name "Net-(U$12-C)") (class "Default")
      (node (ref "C4") (pin "2") (pinfunction "2_2") (pintype "passive"))
      (node (ref "R8") (pin "1") (pinfunction "1_1") (pintype "passive"))
      (node (ref "U$12") (pin "3") (pinfunction "C_3") (pintype "passive"))
    )
    (net (code "71") (name "Net-(U$14-C)") (class "Default")
      (node (ref "U$14") (pin "K") (pinfunction "C_K") (pintype "passive"))
      (node (ref "U$2") (pin "3") (pinfunction "IN_3") (pintype "bidirectional"))
      (node (ref "U$3") (pin "P$2") (pinfunction "+_P$2") (pintype "passive"))
    )
    (net (code "72") (name "Net-(U$15-ACT#)") (class "Default")
      (node (ref "R12") (pin "1") (pinfunction "1_1") (pintype "passive"))
      (node (ref "U$15") (pin "24") (pinfunction "ACT#_24") (pintype "bidirectional"))
    )
    (net (code "73") (name "Net-(U$15-V3)") (class "Default")
      (node (ref "C14") (pin "1") (pinfunction "1_1") (pintype "passive"))
      (node (ref "U$15") (pin "9") (pinfunction "V3_9") (pintype "bidirectional"))
    )
    (net (code "74") (name "Net-(U$15-XI)") (class "Default")
      (node (ref "C19") (pin "1") (pinfunction "1_1") (pintype "passive"))
      (node (ref "Q1") (pin "2") (pinfunction "2_2") (pintype "passive"))
      (node (ref "U$15") (pin "13") (pinfunction "XI_13") (pintype "bidirectional"))
    )
    (net (code "75") (name "Net-(U$15-XO)") (class "Default")
      (node (ref "C20") (pin "1") (pinfunction "1_1") (pintype "passive"))
      (node (ref "Q1") (pin "1") (pinfunction "1_1") (pintype "passive"))
      (node (ref "U$15") (pin "14") (pinfunction "XO_14") (pintype "bidirectional"))
    )
    (net (code "76") (name "unconnected-(IC2B-O-Pad10)") (class "Default")
      (node (ref "IC2") (pin "10") (pinfunction "O_10") (pintype "output"))
    )
    (net (code "77") (name "unconnected-(LINE_IN-PadRING_SWITCH)") (class "Default")
      (node (ref "LINE_IN") (pin "RING_SWITCH") (pinfunction "RING_SWITCH_RING_SWITCH") (pintype "passive"))
    )
    (net (code "78") (name "unconnected-(LINE_IN-PadTIP)") (class "Default")
      (node (ref "LINE_IN") (pin "TIP") (pinfunction "TIP_TIP") (pintype "passive"))
    )
    (net (code "79") (name "unconnected-(LINE_IN-PadTIP_SWITCH)") (class "Default")
      (node (ref "LINE_IN") (pin "TIP_SWITCH") (pinfunction "TIP_SWITCH_TIP_SWITCH") (pintype "passive"))
    )
    (net (code "80") (name "unconnected-(LINE_OUT-PadRING_SWITCH)") (class "Default")
      (node (ref "LINE_OUT") (pin "RING_SWITCH") (pinfunction "RING_SWITCH_RING_SWITCH") (pintype "passive"))
    )
    (net (code "81") (name "unconnected-(LINE_OUT-PadTIP)") (class "Default")
      (node (ref "LINE_OUT") (pin "TIP") (pinfunction "TIP_TIP") (pintype "passive"))
    )
    (net (code "82") (name "unconnected-(LINE_OUT-PadTIP_SWITCH)") (class "Default")
      (node (ref "LINE_OUT") (pin "TIP_SWITCH") (pinfunction "TIP_SWITCH_TIP_SWITCH") (pintype "passive"))
    )
    (net (code "83") (name "unconnected-(MIC_IN-PadRING_SWITCH)") (class "Default")
      (node (ref "MIC_IN") (pin "RING_SWITCH") (pinfunction "RING_SWITCH_RING_SWITCH") (pintype "passive"))
    )
    (net (code "84") (name "unconnected-(MIC_IN-PadTIP)") (class "Default")
      (node (ref "MIC_IN") (pin "TIP") (pinfunction "TIP_TIP") (pintype "passive"))
    )
    (net (code "85") (name "unconnected-(MIC_IN-PadTIP_SWITCH)") (class "Default")
      (node (ref "MIC_IN") (pin "TIP_SWITCH") (pinfunction "TIP_SWITCH_TIP_SWITCH") (pintype "passive"))
    )
    (net (code "86") (name "unconnected-(MIC_OUT-PadRING_SWITCH)") (class "Default")
      (node (ref "MIC_OUT") (pin "RING_SWITCH") (pinfunction "RING_SWITCH_RING_SWITCH") (pintype "passive"))
    )
    (net (code "87") (name "unconnected-(MIC_OUT-PadTIP)") (class "Default")
      (node (ref "MIC_OUT") (pin "TIP") (pinfunction "TIP_TIP") (pintype "passive"))
    )
    (net (code "88") (name "unconnected-(MIC_OUT-PadTIP_SWITCH)") (class "Default")
      (node (ref "MIC_OUT") (pin "TIP_SWITCH") (pinfunction "TIP_SWITCH_TIP_SWITCH") (pintype "passive"))
    )
    (net (code "89") (name "unconnected-(PROGRAM-Pad6)") (class "Default")
      (node (ref "PROGRAM") (pin "6") (pinfunction "6_6") (pintype "passive"))
    )
    (net (code "90") (name "unconnected-(S1-Pad1)") (class "Default")
      (node (ref "S1") (pin "1") (pinfunction "1_1") (pintype "bidirectional"))
    )
    (net (code "91") (name "unconnected-(S1-Pad4)") (class "Default")
      (node (ref "S1") (pin "4") (pinfunction "4_4") (pintype "bidirectional"))
    )
    (net (code "92") (name "unconnected-(S2-Pad1)") (class "Default")
      (node (ref "S2") (pin "1") (pinfunction "1_1") (pintype "bidirectional"))
    )
    (net (code "93") (name "unconnected-(S2-Pad4)") (class "Default")
      (node (ref "S2") (pin "4") (pinfunction "4_4") (pintype "bidirectional"))
    )
    (net (code "94") (name "unconnected-(S3-Pad1)") (class "Default")
      (node (ref "S3") (pin "1") (pinfunction "1_1") (pintype "bidirectional"))
    )
    (net (code "95") (name "unconnected-(S3-Pad4)") (class "Default")
      (node (ref "S3") (pin "4") (pinfunction "4_4") (pintype "bidirectional"))
    )
    (net (code "96") (name "unconnected-(S4-Pad1)") (class "Default")
      (node (ref "S4") (pin "1") (pinfunction "1_1") (pintype "bidirectional"))
    )
    (net (code "97") (name "unconnected-(S4-Pad4)") (class "Default")
      (node (ref "S4") (pin "4") (pinfunction "4_4") (pintype "bidirectional"))
    )
    (net (code "98") (name "unconnected-(S5-Pad1)") (class "Default")
      (node (ref "S5") (pin "1") (pinfunction "1_1") (pintype "bidirectional"))
    )
    (net (code "99") (name "unconnected-(S5-Pad4)") (class "Default")
      (node (ref "S5") (pin "4") (pinfunction "4_4") (pintype "bidirectional"))
    )
    (net (code "100") (name "unconnected-(U$1-NC1-Pad12)") (class "Default")
      (node (ref "U$1") (pin "12") (pinfunction "NC1_12") (pintype "bidirectional"))
    )
    (net (code "101") (name "unconnected-(U$1-NC2-Pad13)") (class "Default")
      (node (ref "U$1") (pin "13") (pinfunction "NC2_13") (pintype "bidirectional"))
    )
    (net (code "102") (name "unconnected-(U$1-NC3-Pad33)") (class "Default")
      (node (ref "U$1") (pin "33") (pinfunction "NC3_33") (pintype "bidirectional"))
    )
    (net (code "103") (name "unconnected-(U$1-NC4-Pad34)") (class "Default")
      (node (ref "U$1") (pin "34") (pinfunction "NC4_34") (pintype "bidirectional"))
    )
    (net (code "104") (name "unconnected-(U$1-RA4{slash}T0CKI{slash}C1OUT-Pad23)") (class "Default")
      (node (ref "U$1") (pin "23") (pinfunction "RA4/T0CKI/C1OUT_23") (pintype "bidirectional"))
    )
    (net (code "105") (name "unconnected-(U$1-RA5{slash}AN4{slash}LVDIN{slash}~{SS{slash}C2OUT}-Pad24)") (class "Default")
      (node (ref "U$1") (pin "24") (pinfunction "RA5/AN4/LVDIN/~{SS/C2OUT}_24") (pintype "bidirectional"))
    )
    (net (code "106") (name "unconnected-(U$1-RC0{slash}T1OSO{slash}T1CKI-Pad32)") (class "Default")
      (node (ref "U$1") (pin "32") (pinfunction "RC0/T1OSO/T1CKI_32") (pintype "bidirectional"))
    )
    (net (code "107") (name "unconnected-(U$1-RC1{slash}T1OSI{slash}CCP2-Pad35)") (class "Default")
      (node (ref "U$1") (pin "35") (pinfunction "RC1/T1OSI/CCP2_35") (pintype "bidirectional"))
    )
    (net (code "108") (name "unconnected-(U$1-RC2{slash}CCP1-Pad36)") (class "Default")
      (node (ref "U$1") (pin "36") (pinfunction "RC2/CCP1_36") (pintype "bidirectional"))
    )
    (net (code "109") (name "unconnected-(U$1-RD0{slash}PSP0-Pad38)") (class "Default")
      (node (ref "U$1") (pin "38") (pinfunction "RD0/PSP0_38") (pintype "bidirectional"))
    )
    (net (code "110") (name "unconnected-(U$1-RD1{slash}PSP1-Pad39)") (class "Default")
      (node (ref "U$1") (pin "39") (pinfunction "RD1/PSP1_39") (pintype "bidirectional"))
    )
    (net (code "111") (name "unconnected-(U$1-RD5{slash}PSP5-Pad3)") (class "Default")
      (node (ref "U$1") (pin "3") (pinfunction "RD5/PSP5_3") (pintype "bidirectional"))
    )
    (net (code "112") (name "unconnected-(U$1-RE0{slash}~{RD{slash}AN5}-Pad25)") (class "Default")
      (node (ref "U$1") (pin "25") (pinfunction "RE0/~{RD/AN5}_25") (pintype "bidirectional"))
    )
    (net (code "113") (name "unconnected-(U$1-RE1{slash}~{WR{slash}AN6}-Pad26)") (class "Default")
      (node (ref "U$1") (pin "26") (pinfunction "RE1/~{WR/AN6}_26") (pintype "bidirectional"))
    )
    (net (code "114") (name "unconnected-(U$1-RE2{slash}~{CS{slash}AN7}-Pad27)") (class "Default")
      (node (ref "U$1") (pin "27") (pinfunction "RE2/~{CS/AN7}_27") (pintype "bidirectional"))
    )
    (net (code "115") (name "unconnected-(U$4-SIO2-Pad3)") (class "Default")
      (node (ref "U$4") (pin "3") (pinfunction "SIO2_3") (pintype "bidirectional"))
    )
    (net (code "116") (name "unconnected-(U$15-BZ{slash}D4-Pad19)") (class "Default")
      (node (ref "U$15") (pin "19") (pinfunction "BZ/D4_19") (pintype "bidirectional"))
    )
    (net (code "117") (name "unconnected-(U$15-D0-Pad15)") (class "Default")
      (node (ref "U$15") (pin "15") (pinfunction "D0_15") (pintype "bidirectional"))
    )
    (net (code "118") (name "unconnected-(U$15-D1-Pad16)") (class "Default")
      (node (ref "U$15") (pin "16") (pinfunction "D1_16") (pintype "bidirectional"))
    )
    (net (code "119") (name "unconnected-(U$15-D2-Pad17)") (class "Default")
      (node (ref "U$15") (pin "17") (pinfunction "D2_17") (pintype "bidirectional"))
    )
    (net (code "120") (name "unconnected-(U$15-SD_CK-Pad26)") (class "Default")
      (node (ref "U$15") (pin "26") (pinfunction "SD_CK_26") (pintype "bidirectional"))
    )
    (net (code "121") (name "unconnected-(U$15-SD_CS-Pad23)") (class "Default")
      (node (ref "U$15") (pin "23") (pinfunction "SD_CS_23") (pintype "bidirectional"))
    )
    (net (code "122") (name "unconnected-(U$15-SD_DI-Pad7)") (class "Default")
      (node (ref "U$15") (pin "7") (pinfunction "SD_DI_7") (pintype "bidirectional"))
    )
    (net (code "123") (name "unconnected-(U$15-SD_DO-Pad25)") (class "Default")
      (node (ref "U$15") (pin "25") (pinfunction "SD_DO_25") (pintype "bidirectional"))
    )
    (net (code "124") (name "unconnected-(X1-Pad1)") (class "Default")
      (node (ref "X1") (pin "1") (pinfunction "1_1") (pintype "passive"))
    )
    (net (code "125") (name "unconnected-(X1-Pad4)") (class "Default")
      (node (ref "X1") (pin "4") (pinfunction "4_4") (pintype "passive"))
    )
    (net (code "126") (name "unconnected-(X1-Pad6)") (class "Default")
      (node (ref "X1") (pin "6") (pinfunction "6_6") (pintype "passive"))
    )
    (net (code "127") (name "unconnected-(X1-Pad9)") (class "Default")
      (node (ref "X1") (pin "9") (pinfunction "9_9") (pintype "passive"))
    )
  )
)
